# asp32.net
KiCad netlist of a schematic drawn in EAGLE
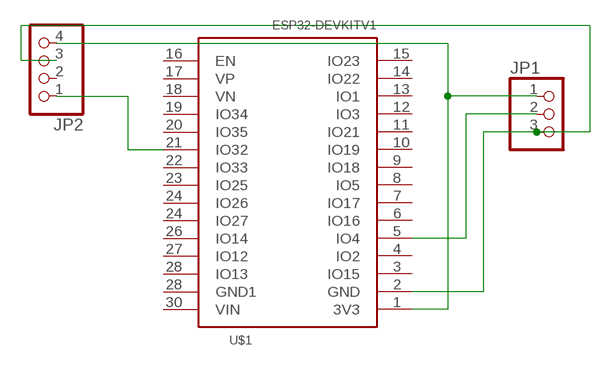
[diagram p0: schematic, sheet 1]

(export (version "E")
  (design (tool "Eeschema 10.0.6"))
  (components
    (comp (ref "JP1")
      (value "PINHD-1X3")
      (footprint "eagle-import:1X03")
      (libsource (lib "eagle-import") (part "PINHD-1X3"))
    )
    (comp (ref "JP2")
      (value "PINHD-1X4")
      (footprint "eagle-import:1X04")
      (libsource (lib "eagle-import") (part "PINHD-1X4"))
    )
    (comp (ref "U$1")
      (value "ESP32DEVKITV1")
      (footprint "eagle-import:ESP32-DEVKITV1")
      (libsource (lib "eagle-import") (part "ESP32DEVKITV1"))
    )
  )
  (nets
    (net (code "1") (name "Net-(U$1-3V3)") (class "Default")
      (node (ref "JP1") (pin "1") (pinfunction "1_1") (pintype "passive"))
      (node (ref "JP2") (pin "4") (pinfunction "4_4") (pintype "passive"))
      (node (ref "U$1") (pin "1") (pinfunction "3V3_1") (pintype "bidirectional"))
    )
    (net (code "2") (name "Net-(U$1-GND)") (class "Default")
      (node (ref "JP1") (pin "3") (pinfunction "3_3") (pintype "passive"))
      (node (ref "JP2") (pin "3") (pinfunction "3_3") (pintype "passive"))
      (node (ref "U$1") (pin "2") (pinfunction "GND_2") (pintype "bidirectional"))
    )
    (net (code "3") (name "Net-(U$1-IO4)") (class "Default")
      (node (ref "JP1") (pin "2") (pinfunction "2_2") (pintype "passive"))
      (node (ref "U$1") (pin "5") (pinfunction "IO4_5") (pintype "bidirectional"))
    )
    (net (code "4") (name "Net-(U$1-IO32)") (class "Default")
      (node (ref "JP2") (pin "1") (pinfunction "1_1") (pintype "passive"))
      (node (ref "U$1") (pin "21") (pinfunction "IO32_21") (pintype "bidirectional"))
    )
    (net (code "5") (name "unconnected-(JP2-Pad2)") (class "Default")
      (node (ref "JP2") (pin "2") (pinfunction "2_2") (pintype "passive"))
    )
    (net (code "6") (name "unconnected-(U$1-EN-Pad16)") (class "Default")
      (node (ref "U$1") (pin "16") (pinfunction "EN_16") (pintype "bidirectional"))
    )
    (net (code "7") (name "unconnected-(U$1-GND1-Pad28)") (class "Default")
      (node (ref "U$1") (pin "28") (pinfunction "GND1_28") (pintype "bidirectional"))
    )
    (net (code "8") (name "unconnected-(U$1-IO1-Pad13)") (class "Default")
      (node (ref "U$1") (pin "13") (pinfunction "IO1_13") (pintype "bidirectional"))
    )
    (net (code "9") (name "unconnected-(U$1-IO2-Pad4)") (class "Default")
      (node (ref "U$1") (pin "4") (pinfunction "IO2_4") (pintype "bidirectional"))
    )
    (net (code "10") (name "unconnected-(U$1-IO3-Pad12)") (class "Default")
      (node (ref "U$1") (pin "12") (pinfunction "IO3_12") (pintype "bidirectional"))
    )
    (net (code "11") (name "unconnected-(U$1-IO5-Pad8)") (class "Default")
      (node (ref "U$1") (pin "8") (pinfunction "IO5_8") (pintype "bidirectional"))
    )
    (net (code "12") (name "unconnected-(U$1-IO12-Pad27)") (class "Default")
      (node (ref "U$1") (pin "27") (pinfunction "IO12_27") (pintype "bidirectional"))
    )
    (net (code "13") (name "unconnected-(U$1-IO13-Pad28)") (class "Default")
      (node (ref "U$1") (pin "28") (pinfunction "IO13_28") (pintype "bidirectional"))
    )
    (net (code "14") (name "unconnected-(U$1-IO14-Pad26)") (class "Default")
      (node (ref "U$1") (pin "26") (pinfunction "IO14_26") (pintype "bidirectional"))
    )
    (net (code "15") (name "unconnected-(U$1-IO15-Pad3)") (class "Default")
      (node (ref "U$1") (pin "3") (pinfunction "IO15_3") (pintype "bidirectional"))
    )
    (net (code "16") (name "unconnected-(U$1-IO16-Pad6)") (class "Default")
      (node (ref "U$1") (pin "6") (pinfunction "IO16_6") (pintype "bidirectional"))
    )
    (net (code "17") (name "unconnected-(U$1-IO17-Pad7)") (class "Default")
      (node (ref "U$1") (pin "7") (pinfunction "IO17_7") (pintype "bidirectional"))
    )
    (net (code "18") (name "unconnected-(U$1-IO18-Pad9)") (class "Default")
      (node (ref "U$1") (pin "9") (pinfunction "IO18_9") (pintype "bidirectional"))
    )
    (net (code "19") (name "unconnected-(U$1-IO19-Pad10)") (class "Default")
      (node (ref "U$1") (pin "10") (pinfunction "IO19_10") (pintype "bidirectional"))
    )
    (net (code "20") (name "unconnected-(U$1-IO21-Pad11)") (class "Default")
      (node (ref "U$1") (pin "11") (pinfunction "IO21_11") (pintype "bidirectional"))
    )
    (net (code "21") (name "unconnected-(U$1-IO22-Pad14)") (class "Default")
      (node (ref "U$1") (pin "14") (pinfunction "IO22_14") (pintype "bidirectional"))
    )
    (net (code "22") (name "unconnected-(U$1-IO23-Pad15)") (class "Default")
      (node (ref "U$1") (pin "15") (pinfunction "IO23_15") (pintype "bidirectional"))
    )
    (net (code "23") (name "unconnected-(U$1-IO25-Pad23)") (class "Default")
      (node (ref "U$1") (pin "23") (pinfunction "IO25_23") (pintype "bidirectional"))
    )
    (net (code "24") (name "unconnected-(U$1-IO26-Pad24)") (class "Default")
      (node (ref "U$1") (pin "24") (pinfunction "IO26_24") (pintype "bidirectional"))
    )
    (net (code "25") (name "unconnected-(U$1-IO27-Pad24)") (class "Default")
      (node (ref "U$1") (pin "24") (pinfunction "IO27_24") (pintype "bidirectional"))
    )
    (net (code "26") (name "unconnected-(U$1-IO33-Pad22)") (class "Default")
      (node (ref "U$1") (pin "22") (pinfunction "IO33_22") (pintype "bidirectional"))
    )
    (net (code "27") (name "unconnected-(U$1-IO34-Pad19)") (class "Default")
      (node (ref "U$1") (pin "19") (pinfunction "IO34_19") (pintype "bidirectional"))
    )
    (net (code "28") (name "unconnected-(U$1-IO35-Pad20)") (class "Default")
      (node (ref "U$1") (pin "20") (pinfunction "IO35_20") (pintype "bidirectional"))
    )
    (net (code "29") (name "unconnected-(U$1-VIN-Pad30)") (class "Default")
      (node (ref "U$1") (pin "30") (pinfunction "VIN_30") (pintype "bidirectional"))
    )
    (net (code "30") (name "unconnected-(U$1-VN-Pad18)") (class "Default")
      (node (ref "U$1") (pin "18") (pinfunction "VN_18") (pintype "bidirectional"))
    )
    (net (code "31") (name "unconnected-(U$1-VP-Pad17)") (class "Default")
      (node (ref "U$1") (pin "17") (pinfunction "VP_17") (pintype "bidirectional"))
    )
  )
)
